# Battery_Manager.net
KiCad netlist of a schematic drawn in Altium Designer
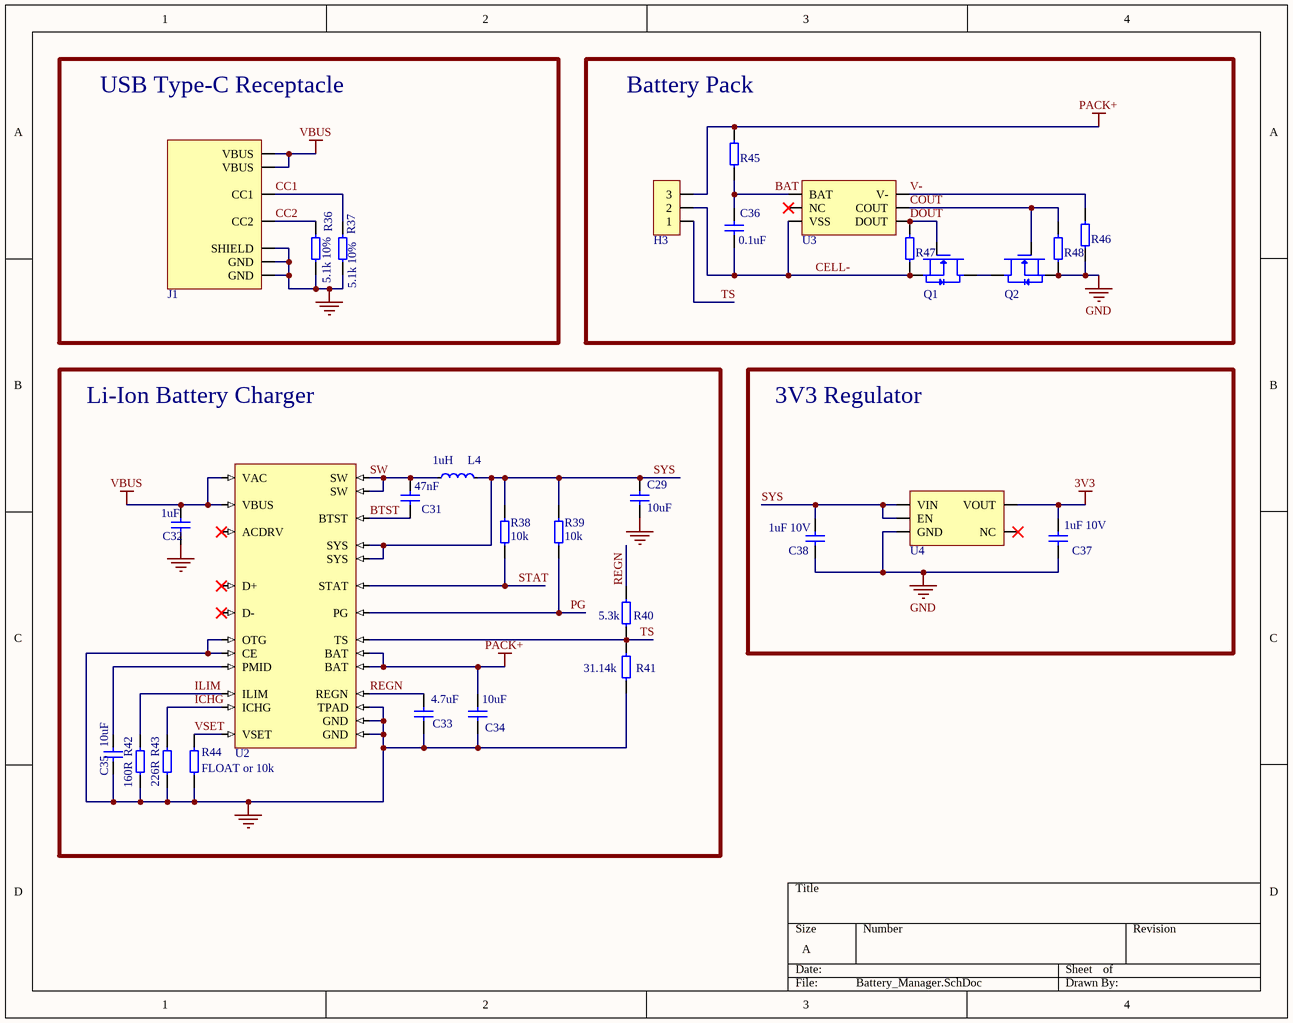
[diagram p0: Battery_Manager.SchDoc]

(export (version "E")
  (design (tool "Eeschema 10.0.6"))
  (components
    (comp (ref "C29")
      (value "10uF")
      (footprint "0603 Capacitor")
      (libsource (lib "MoldsvorLibrary") (part "Capacitor"))
    )
    (comp (ref "C31")
      (value "47nF")
      (footprint "0603 Capacitor")
      (libsource (lib "MoldsvorLibrary") (part "Capacitor"))
    )
    (comp (ref "C32")
      (value "1uF")
      (footprint "0603 Capacitor")
      (libsource (lib "MoldsvorLibrary") (part "Capacitor"))
    )
    (comp (ref "C33")
      (value "4.7uF")
      (footprint "0603 Capacitor")
      (libsource (lib "MoldsvorLibrary") (part "Capacitor"))
    )
    (comp (ref "C34")
      (value "10uF")
      (footprint "0603 Capacitor")
      (libsource (lib "MoldsvorLibrary") (part "Capacitor"))
    )
    (comp (ref "C35")
      (value "10uF")
      (footprint "0603 Capacitor")
      (libsource (lib "MoldsvorLibrary") (part "Capacitor"))
    )
    (comp (ref "C36")
      (value "0.1uF")
      (footprint "0603 Capacitor")
      (libsource (lib "MoldsvorLibrary") (part "Capacitor"))
    )
    (comp (ref "C37")
      (value "1uF 10V")
      (footprint "0603 Capacitor")
      (libsource (lib "MoldsvorLibrary") (part "Capacitor"))
    )
    (comp (ref "C38")
      (value "1uF 10V")
      (footprint "0603 Capacitor")
      (libsource (lib "MoldsvorLibrary") (part "Capacitor"))
    )
    (comp (ref "H3")
      (value "22-05-7035")
      (footprint "Molex Header 3")
      (description "Header 2.5mm SPOX,  WTB,  RA,  F/lock,  3w")
      (libsource (lib "MoldsvorLibrary") (part "22-05-7035"))
    )
    (comp (ref "J1")
      (value "USB4125-GF-A")
      (footprint "USB4125")
      (description "Conn Rcp USB2.0 Typ C 24P SMD Ra")
      (libsource (lib "MoldsvorLibrary") (part "USB4125-GF-A"))
    )
    (comp (ref "L4")
      (value "1uH")
      (footprint "SRP2510A")
      (description "BOURNS - SRP2510A-1R0M - INDUCTOR, 1UH, 3A, 20%, SHIELDED")
      (fields (field (name "TOLERANCE") "20%"))
      (libsource (lib "MoldsvorLibrary") (part "SRP2510A-1R0M"))
    )
    (comp (ref "Q1")
      (value "CSD16406Q3")
      (footprint "CSD16406Q3")
      (description "TEXAS INSTRUMENTS - CSD16406Q3 - N CHANNEL MOSFET, 25V, 60A, SON")
      (libsource (lib "MoldsvorLibrary") (part "CSD16406Q3"))
    )
    (comp (ref "Q2")
      (value "CSD16406Q3")
      (footprint "CSD16406Q3")
      (description "TEXAS INSTRUMENTS - CSD16406Q3 - N CHANNEL MOSFET, 25V, 60A, SON")
      (libsource (lib "MoldsvorLibrary") (part "CSD16406Q3"))
    )
    (comp (ref "R36")
      (value "5.1k 10%")
      (footprint "0603 Resistor")
      (libsource (lib "MoldsvorLibrary") (part "Resistor"))
    )
    (comp (ref "R37")
      (value "5.1k 10%")
      (footprint "0603 Resistor")
      (libsource (lib "MoldsvorLibrary") (part "Resistor"))
    )
    (comp (ref "R38")
      (value "10k")
      (footprint "0603 Resistor")
      (libsource (lib "MoldsvorLibrary") (part "Resistor"))
    )
    (comp (ref "R39")
      (value "10k")
      (footprint "0603 Resistor")
      (libsource (lib "MoldsvorLibrary") (part "Resistor"))
    )
    (comp (ref "R40")
      (value "5.3k")
      (footprint "0603 Resistor")
      (libsource (lib "MoldsvorLibrary") (part "Resistor"))
    )
    (comp (ref "R41")
      (value "31.14k")
      (footprint "0603 Resistor")
      (libsource (lib "MoldsvorLibrary") (part "Resistor"))
    )
    (comp (ref "R42")
      (value "160R")
      (footprint "0603 Resistor")
      (libsource (lib "MoldsvorLibrary") (part "Resistor"))
    )
    (comp (ref "R43")
      (value "226R")
      (footprint "0603 Resistor")
      (libsource (lib "MoldsvorLibrary") (part "Resistor"))
    )
    (comp (ref "R44")
      (value "FLOAT or 10k")
      (footprint "0603 Resistor")
      (libsource (lib "MoldsvorLibrary") (part "Resistor"))
    )
    (comp (ref "R45")
      (value "330R")
      (footprint "0603 Resistor")
      (libsource (lib "MoldsvorPassivesLibrary") (part "Resistor"))
    )
    (comp (ref "R46")
      (value "2.2k")
      (footprint "0603 Resistor")
      (libsource (lib "MoldsvorPassivesLibrary") (part "Resistor"))
    )
    (comp (ref "R47")
      (value "5M")
      (footprint "0603 Resistor")
      (libsource (lib "MoldsvorPassivesLibrary") (part "Resistor"))
    )
    (comp (ref "R48")
      (value "5M")
      (footprint "0603 Resistor")
      (libsource (lib "MoldsvorPassivesLibrary") (part "Resistor"))
    )
    (comp (ref "U2")
      (value "BQ25616JRTWR")
      (footprint "BQ25616")
      (libsource (lib "MoldsvorBatteryLibrary") (part "BQ25616JRTWR"))
    )
    (comp (ref "U3")
      (value "BQ29700DSET")
      (footprint "BQ297xx")
      (description "Li-Ion/Li Polymer Advanced Single-Cell Battery Protector IC Family 6-WSON -40 to 85")
      (libsource (lib "MoldsvorLibrary") (part "BQ29700DSET"))
    )
    (comp (ref "U4")
      (value "MIC5504-3.3YM5-TR")
      (footprint "MIC5504")
      (description "MICROCHIP - MIC5504-3.3YM5-TR - LDO VOLT REG, 0.3A, 3.3V, SOT-23-5")
      (libsource (lib "Gamepad_Schematic_Library") (part "MIC5504-3.3YM5-TR"))
    )
  )
  (nets
    (net (code "1") (name "/BAT") (class "Default")
      (node (ref "C36") (pin "2") (pinfunction "2_2") (pintype "passive"))
      (node (ref "R45") (pin "1") (pintype "passive"))
      (node (ref "U3") (pin "5") (pinfunction "BAT_5") (pintype "passive"))
    )
    (net (code "2") (name "/BTST") (class "Default")
      (node (ref "C31") (pin "1") (pinfunction "1_1") (pintype "passive"))
      (node (ref "U2") (pin "21") (pinfunction "BTST_21") (pintype "input"))
    )
    (net (code "3") (name "/CC1") (class "Default")
      (node (ref "J1") (pin "A5") (pinfunction "CC1_A5") (pintype "passive"))
      (node (ref "R37") (pin "2") (pintype "passive"))
    )
    (net (code "4") (name "/CC2") (class "Default")
      (node (ref "J1") (pin "B5") (pinfunction "CC2_B5") (pintype "passive"))
      (node (ref "R36") (pin "2") (pintype "passive"))
    )
    (net (code "5") (name "/CELL-") (class "Default")
      (node (ref "C36") (pin "1") (pinfunction "1_1") (pintype "passive"))
      (node (ref "H3") (pin "2") (pinfunction "2_2") (pintype "passive"))
      (node (ref "Q1") (pin "1") (pinfunction "1_1") (pintype "passive"))
      (node (ref "R47") (pin "1") (pintype "passive"))
      (node (ref "U3") (pin "4") (pinfunction "VSS_4") (pintype "passive"))
    )
    (net (code "6") (name "/COUT") (class "Default")
      (node (ref "Q2") (pin "4") (pinfunction "4_4") (pintype "passive"))
      (node (ref "R48") (pin "2") (pintype "passive"))
      (node (ref "U3") (pin "2") (pinfunction "COUT_2") (pintype "passive"))
    )
    (net (code "7") (name "/DOUT") (class "Default")
      (node (ref "Q1") (pin "4") (pinfunction "4_4") (pintype "passive"))
      (node (ref "R47") (pin "2") (pintype "passive"))
      (node (ref "U3") (pin "3") (pinfunction "DOUT_3") (pintype "passive"))
    )
    (net (code "8") (name "/ICHG") (class "Default")
      (node (ref "R43") (pin "2") (pintype "passive"))
      (node (ref "U2") (pin "10") (pinfunction "ICHG_10") (pintype "input"))
    )
    (net (code "9") (name "/ILIM") (class "Default")
      (node (ref "R42") (pin "2") (pintype "passive"))
      (node (ref "U2") (pin "8") (pinfunction "ILIM_8") (pintype "input"))
    )
    (net (code "10") (name "/PG") (class "Default")
      (node (ref "R39") (pin "1") (pintype "passive"))
      (node (ref "U2") (pin "7") (pinfunction "PG_7") (pintype "input"))
    )
    (net (code "11") (name "/REGN") (class "Default")
      (node (ref "C33") (pin "2") (pinfunction "2_2") (pintype "passive"))
      (node (ref "R40") (pin "2") (pintype "passive"))
      (node (ref "U2") (pin "22") (pinfunction "REGN_22") (pintype "input"))
    )
    (net (code "12") (name "/STAT") (class "Default")
      (node (ref "R38") (pin "1") (pintype "passive"))
      (node (ref "U2") (pin "5") (pinfunction "STAT_5") (pintype "input"))
    )
    (net (code "13") (name "/SW") (class "Default")
      (node (ref "C31") (pin "2") (pinfunction "2_2") (pintype "passive"))
      (node (ref "L4") (pin "1") (pinfunction "1_1") (pintype "passive"))
      (node (ref "U2") (pin "19") (pinfunction "SW_19") (pintype "input"))
      (node (ref "U2") (pin "20") (pinfunction "SW_20") (pintype "input"))
    )
    (net (code "14") (name "/SYS") (class "Default")
      (node (ref "C29") (pin "2") (pinfunction "2_2") (pintype "passive"))
      (node (ref "C38") (pin "2") (pinfunction "2_2") (pintype "passive"))
      (node (ref "L4") (pin "2") (pinfunction "2_2") (pintype "passive"))
      (node (ref "R38") (pin "2") (pintype "passive"))
      (node (ref "R39") (pin "2") (pintype "passive"))
      (node (ref "U2") (pin "15") (pinfunction "SYS_15") (pintype "input"))
      (node (ref "U2") (pin "16") (pinfunction "SYS_16") (pintype "input"))
      (node (ref "U4") (pin "1") (pinfunction "VIN_1") (pintype "passive"))
      (node (ref "U4") (pin "3") (pinfunction "EN_3") (pintype "passive"))
    )
    (net (code "15") (name "/TS") (class "Default")
      (node (ref "H3") (pin "1") (pinfunction "1_1") (pintype "passive"))
      (node (ref "R40") (pin "1") (pintype "passive"))
      (node (ref "R41") (pin "2") (pintype "passive"))
      (node (ref "U2") (pin "11") (pinfunction "TS_11") (pintype "input"))
    )
    (net (code "16") (name "/V-") (class "Default")
      (node (ref "R46") (pin "2") (pintype "passive"))
      (node (ref "U3") (pin "6") (pinfunction "V-_6") (pintype "passive"))
    )
    (net (code "17") (name "/VSET") (class "Default")
      (node (ref "R44") (pin "2") (pintype "passive"))
      (node (ref "U2") (pin "12") (pinfunction "VSET_12") (pintype "input"))
    )
    (net (code "18") (name "3V3") (class "Default")
      (node (ref "C37") (pin "2") (pinfunction "2_2") (pintype "passive"))
      (node (ref "U4") (pin "5") (pinfunction "VOUT_5") (pintype "passive"))
    )
    (net (code "19") (name "GND") (class "Default")
      (node (ref "C29") (pin "1") (pinfunction "1_1") (pintype "passive"))
      (node (ref "C32") (pin "1") (pinfunction "1_1") (pintype "passive"))
      (node (ref "C33") (pin "1") (pinfunction "1_1") (pintype "passive"))
      (node (ref "C34") (pin "1") (pinfunction "1_1") (pintype "passive"))
      (node (ref "C35") (pin "1") (pinfunction "1_1") (pintype "passive"))
      (node (ref "C37") (pin "1") (pinfunction "1_1") (pintype "passive"))
      (node (ref "C38") (pin "1") (pinfunction "1_1") (pintype "passive"))
      (node (ref "J1") (pin "A12") (pinfunction "GND_A12") (pintype "passive"))
      (node (ref "J1") (pin "B12") (pinfunction "GND_B12") (pintype "passive"))
      (node (ref "J1") (pin "SHIELD") (pinfunction "SHIELD_SHIELD") (pintype "passive"))
      (node (ref "Q2") (pin "1") (pinfunction "1_1") (pintype "passive"))
      (node (ref "R36") (pin "1") (pintype "passive"))
      (node (ref "R37") (pin "1") (pintype "passive"))
      (node (ref "R41") (pin "1") (pintype "passive"))
      (node (ref "R42") (pin "1") (pintype "passive"))
      (node (ref "R43") (pin "1") (pintype "passive"))
      (node (ref "R44") (pin "1") (pintype "passive"))
      (node (ref "R46") (pin "1") (pintype "passive"))
      (node (ref "R48") (pin "1") (pintype "passive"))
      (node (ref "U2") (pin "17") (pinfunction "GND_17") (pintype "input"))
      (node (ref "U2") (pin "18") (pinfunction "GND_18") (pintype "input"))
      (node (ref "U2") (pin "25") (pinfunction "TPAD_25") (pintype "input"))
      (node (ref "U2") (pin "6") (pinfunction "OTG_6") (pintype "input"))
      (node (ref "U2") (pin "9") (pinfunction "CE_9") (pintype "input"))
      (node (ref "U4") (pin "2") (pinfunction "GND_2") (pintype "passive"))
    )
    (net (code "20") (name "Net-(Q1-Pad5)") (class "Default")
      (node (ref "Q1") (pin "5") (pinfunction "5_5") (pintype "passive"))
      (node (ref "Q2") (pin "5") (pinfunction "5_5") (pintype "passive"))
    )
    (net (code "21") (name "Net-(U2-PMID)") (class "Default")
      (node (ref "C35") (pin "2") (pinfunction "2_2") (pintype "passive"))
      (node (ref "U2") (pin "23") (pinfunction "PMID_23") (pintype "input"))
    )
    (net (code "22") (name "PACK+") (class "Default")
      (node (ref "C34") (pin "2") (pinfunction "2_2") (pintype "passive"))
      (node (ref "H3") (pin "3") (pinfunction "3_3") (pintype "passive"))
      (node (ref "R45") (pin "2") (pintype "passive"))
      (node (ref "U2") (pin "13") (pinfunction "BAT_13") (pintype "input"))
      (node (ref "U2") (pin "14") (pinfunction "BAT_14") (pintype "input"))
    )
    (net (code "23") (name "VBUS") (class "Default")
      (node (ref "C32") (pin "2") (pinfunction "2_2") (pintype "passive"))
      (node (ref "J1") (pin "A9") (pinfunction "VBUS_A9") (pintype "passive"))
      (node (ref "J1") (pin "B9") (pinfunction "VBUS_B9") (pintype "passive"))
      (node (ref "U2") (pin "1") (pinfunction "VAC_1") (pintype "input"))
      (node (ref "U2") (pin "24") (pinfunction "VBUS_24") (pintype "input"))
    )
    (net (code "24") (name "unconnected-(U2-ACDRV-Pad2)") (class "Default")
      (node (ref "U2") (pin "2") (pinfunction "ACDRV_2") (pintype "input+no_connect"))
    )
    (net (code "25") (name "unconnected-(U2-D+-Pad3)") (class "Default")
      (node (ref "U2") (pin "3") (pinfunction "D+_3") (pintype "input+no_connect"))
    )
    (net (code "26") (name "unconnected-(U2-D--Pad4)") (class "Default")
      (node (ref "U2") (pin "4") (pinfunction "D-_4") (pintype "input+no_connect"))
    )
    (net (code "27") (name "unconnected-(U3-NC-Pad1)") (class "Default")
      (node (ref "U3") (pin "1") (pinfunction "NC_1") (pintype "passive+no_connect"))
    )
    (net (code "28") (name "unconnected-(U4-NC-Pad4)") (class "Default")
      (node (ref "U4") (pin "4") (pinfunction "NC_4") (pintype "passive+no_connect"))
    )
  )
)
